# SCHEMA.net
KiCad netlist of a schematic drawn in EasyEDA
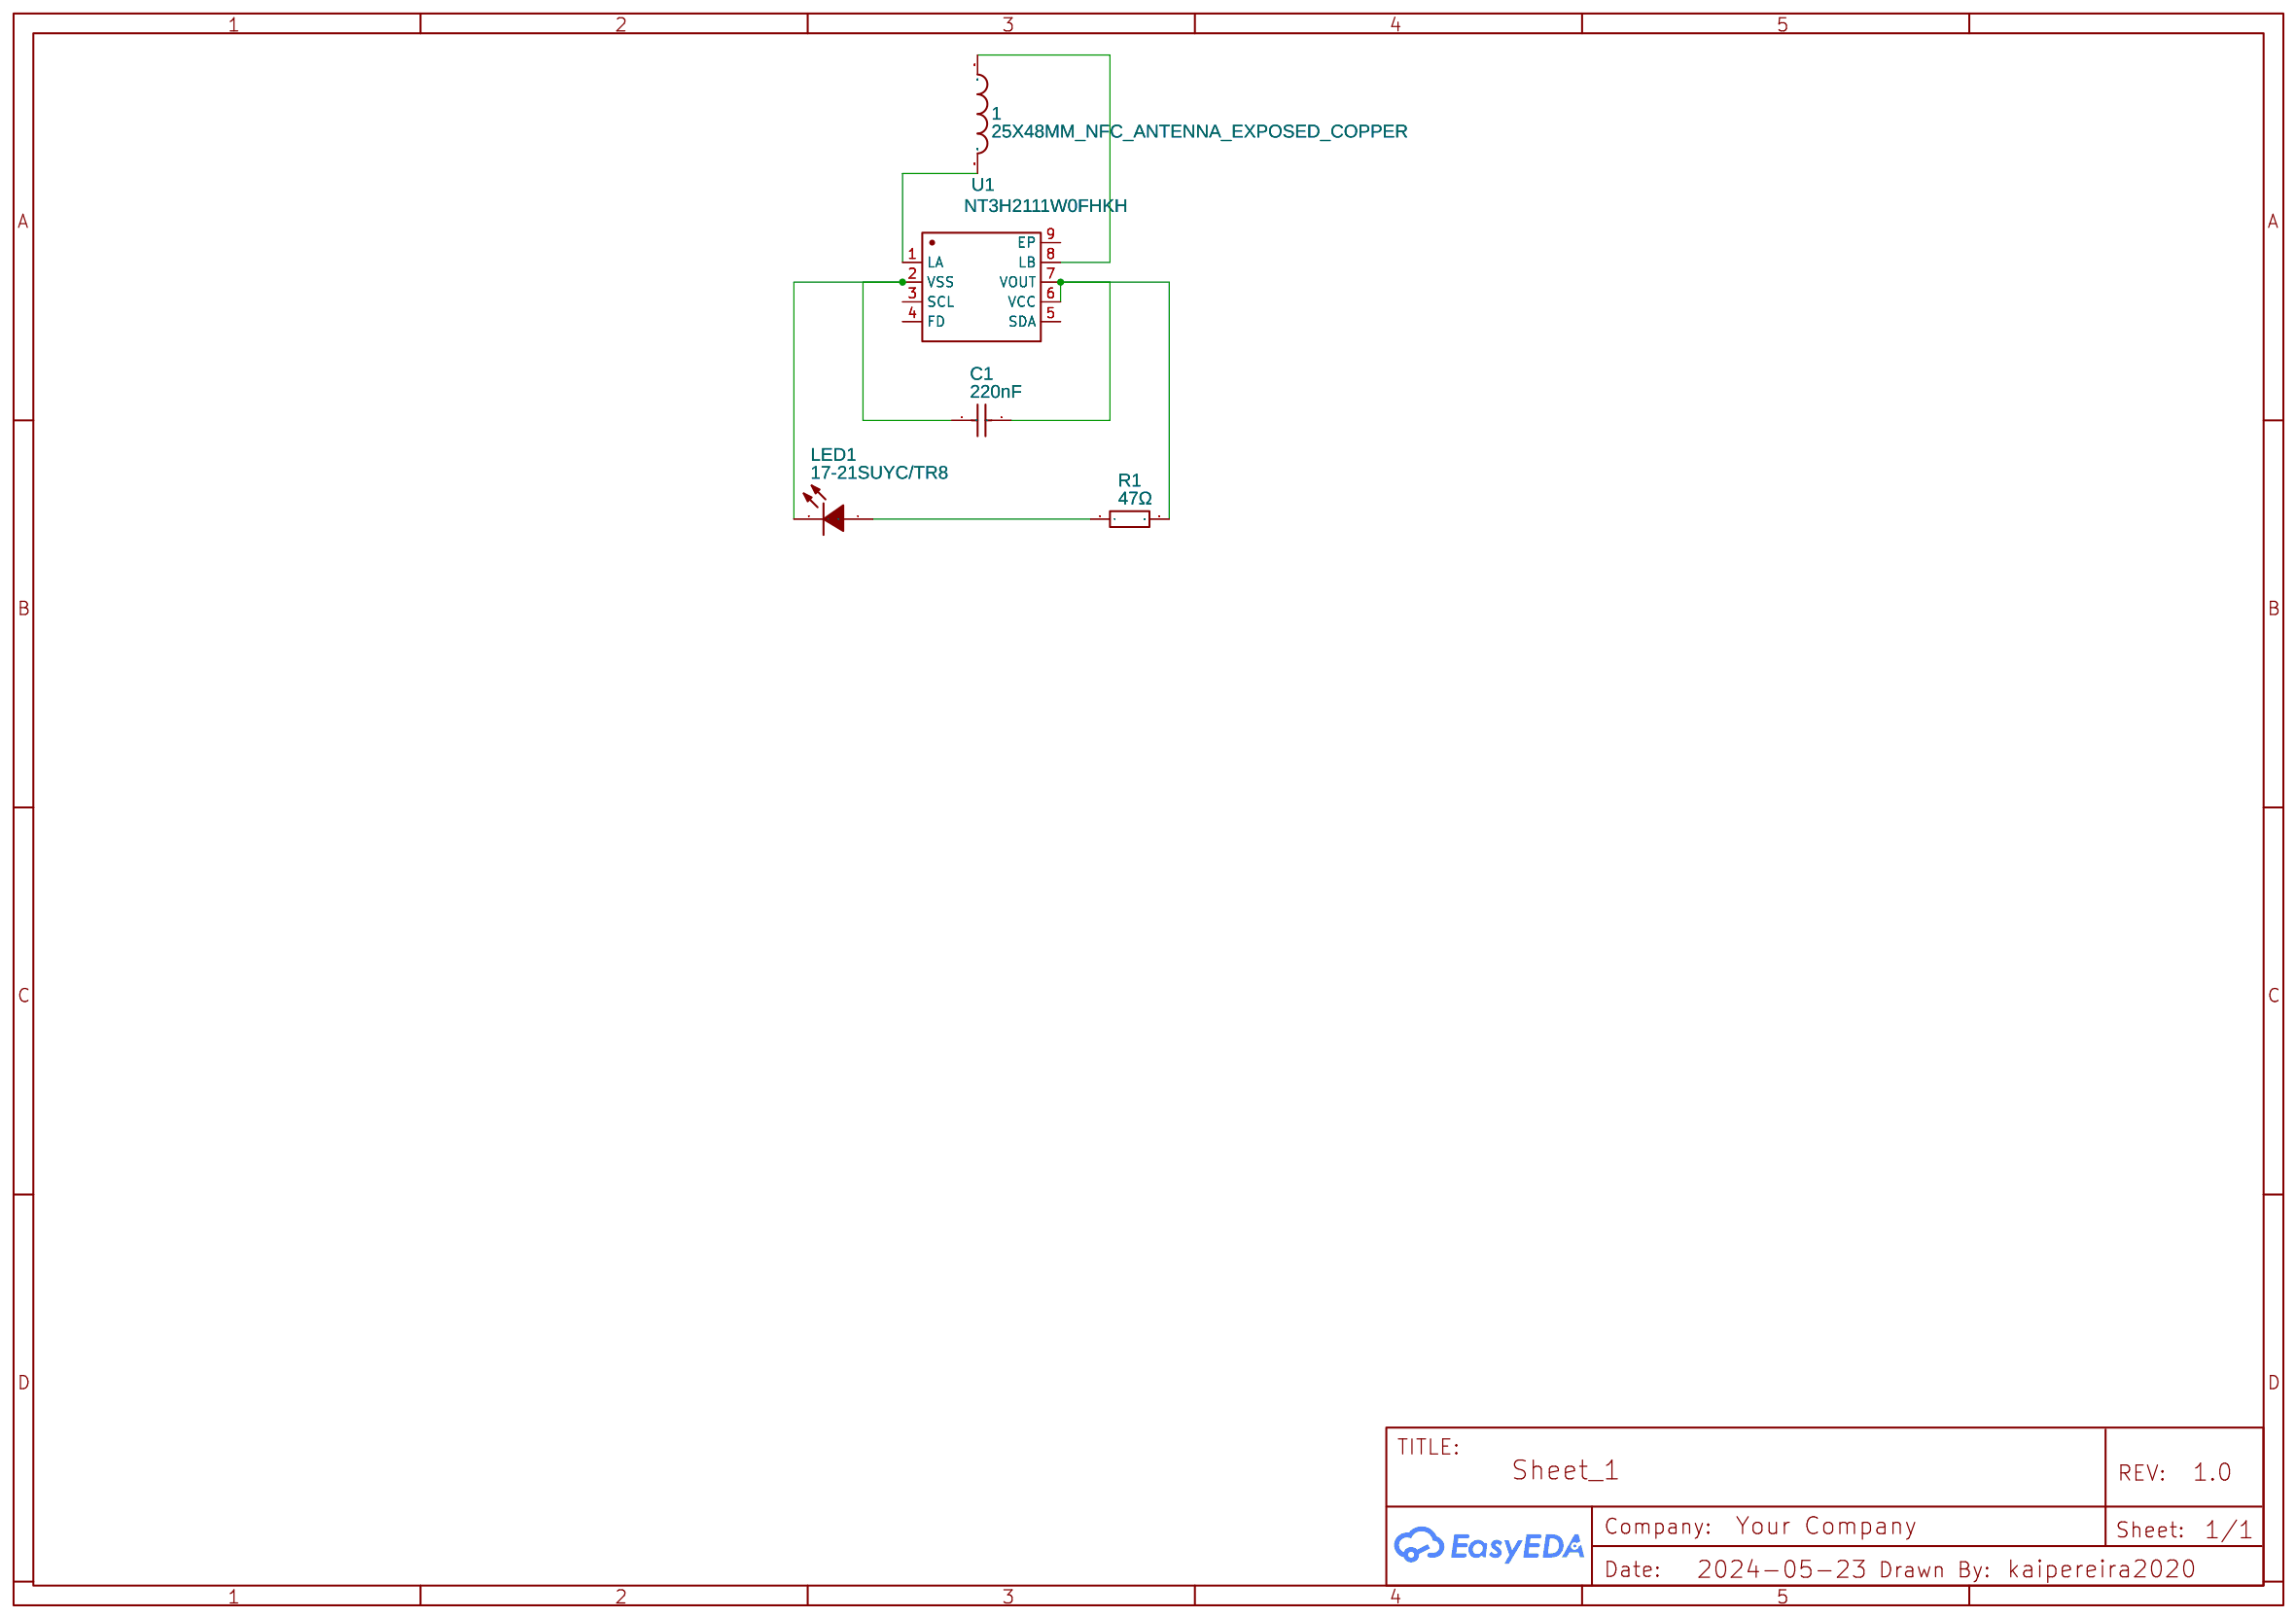
[diagram p0: schematic sheet]

(export (version "E")
  (design (tool "Eeschema 10.0.6"))
  (components
    (comp (ref "1")
      (value "25X48MM_NFC_ANTENNA_EXPOSED_COPPER")
      (libsource (lib "") (part "25X48MM_NFC_ANTENNA_EXPOSED_COPPER"))
    )
    (comp (ref "C1")
      (value "220nF")
      (fields
        (field (name "Manufacturer Part") "CL10B224KA8NNNC")
        (field (name "Manufacturer") "SAMSUNG(三星)")
      )
      (libsource (lib "") (part "CL10B224KA8NNNC"))
    )
    (comp (ref "LED1")
      (value "17-21SUYC/TR8")
      (fields (field (name "Manufacturer Part") "KT-0805黄灯") (field (name "Manufacturer") "KENTO"))
      (libsource (lib "") (part "17-21SUYC/TR8"))
    )
    (comp (ref "R1")
      (value "47Ω")
      (fields
        (field (name "Manufacturer Part") "0603WAF470JT5E")
        (field (name "Manufacturer") "UNI-ROYAL(厚声)")
      )
      (libsource (lib "") (part "0603WAF470JT5E"))
    )
    (comp (ref "U1")
      (value "NT3H2111W0FHKH")
      (fields (field (name "Manufacturer") "NXP(恩智浦)"))
      (libsource (lib "") (part "NT3H2111W0FHKH"))
    )
  )
  (nets
    (net (code "1") (name "Net-(LED1-+)") (class "Default")
      (node (ref "LED1") (pin "1") (pinfunction "+_1") (pintype "unspecified"))
      (node (ref "R1") (pin "1") (pinfunction "1_1") (pintype "input"))
    )
    (net (code "2") (name "Net-(LED1--)") (class "Default")
      (node (ref "C1") (pin "1") (pinfunction "1_1") (pintype "input"))
      (node (ref "LED1") (pin "2") (pinfunction "-_2") (pintype "unspecified"))
      (node (ref "U1") (pin "2") (pinfunction "VSS_2") (pintype "unspecified"))
    )
    (net (code "3") (name "Net-(U1-LA)") (class "Default")
      (node (ref "1") (pin "P$2") (pinfunction "P$2_P$2") (pintype "bidirectional"))
      (node (ref "U1") (pin "1") (pinfunction "LA_1") (pintype "unspecified"))
    )
    (net (code "4") (name "Net-(U1-LB)") (class "Default")
      (node (ref "1") (pin "P$1") (pinfunction "P$1_P$1") (pintype "bidirectional"))
      (node (ref "U1") (pin "8") (pinfunction "LB_8") (pintype "unspecified"))
    )
    (net (code "5") (name "Net-(U1-VCC)") (class "Default")
      (node (ref "C1") (pin "2") (pinfunction "2_2") (pintype "input"))
      (node (ref "R1") (pin "2") (pinfunction "2_2") (pintype "input"))
      (node (ref "U1") (pin "6") (pinfunction "VCC_6") (pintype "unspecified"))
      (node (ref "U1") (pin "7") (pinfunction "VOUT_7") (pintype "unspecified"))
    )
    (net (code "6") (name "unconnected-(U1-EP-Pad9)") (class "Default")
      (node (ref "U1") (pin "9") (pinfunction "EP_9") (pintype "unspecified"))
    )
    (net (code "7") (name "unconnected-(U1-FD-Pad4)") (class "Default")
      (node (ref "U1") (pin "4") (pinfunction "FD_4") (pintype "unspecified"))
    )
    (net (code "8") (name "unconnected-(U1-SCL-Pad3)") (class "Default")
      (node (ref "U1") (pin "3") (pinfunction "SCL_3") (pintype "unspecified"))
    )
    (net (code "9") (name "unconnected-(U1-SDA-Pad5)") (class "Default")
      (node (ref "U1") (pin "5") (pinfunction "SDA_5") (pintype "unspecified"))
    )
  )
)
